# 09sata.net
KiCad netlist of a schematic drawn in Altium Designer
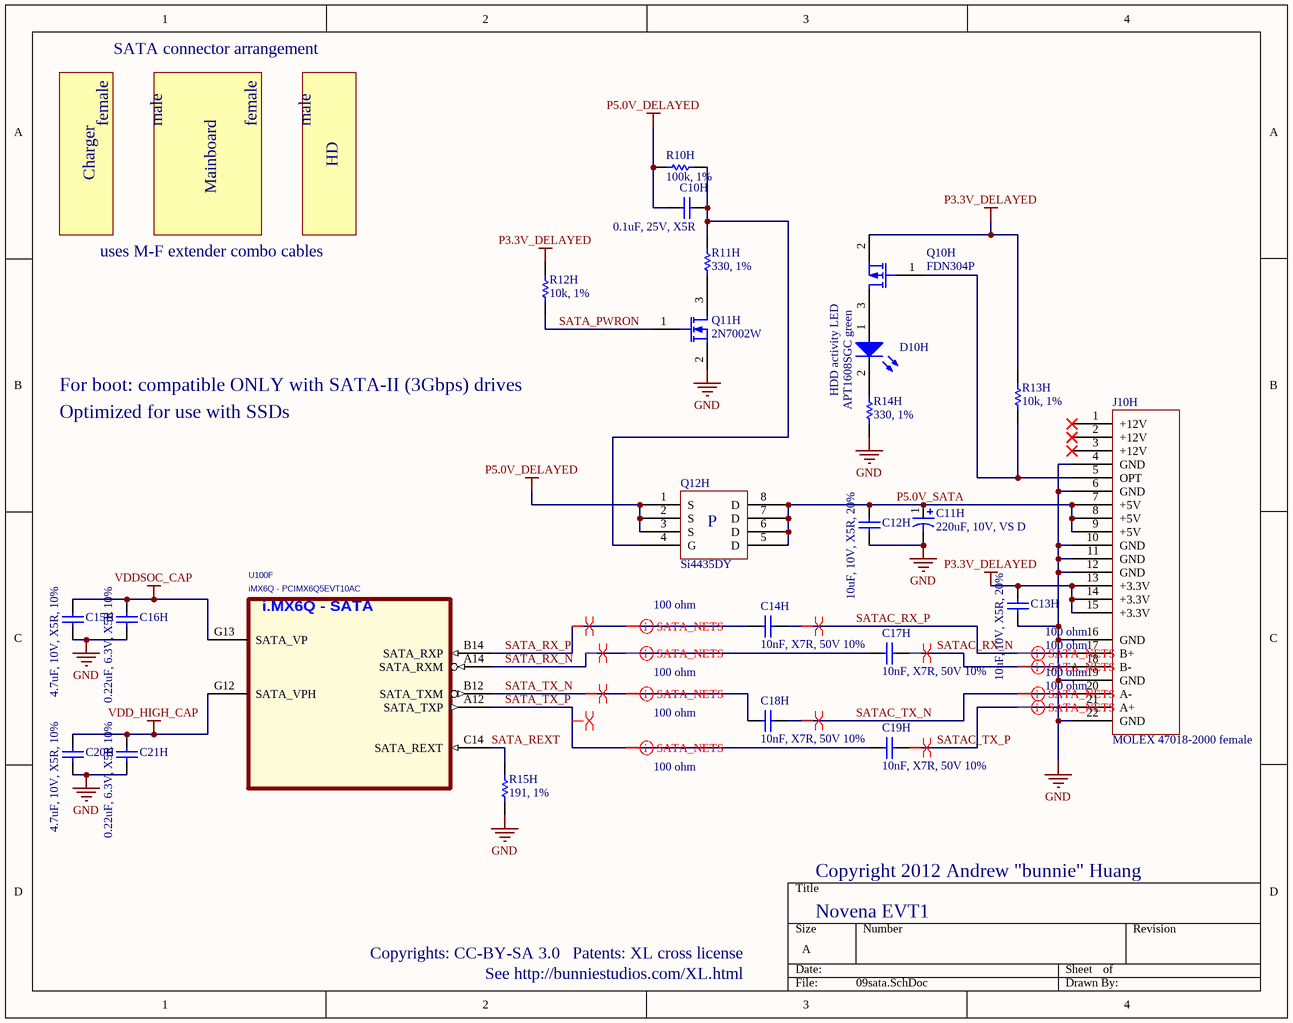
[diagram p0: 09sata.SchDoc]

(export (version "E")
  (design (tool "Eeschema 10.0.6"))
  (components
    (comp (ref "C10H")
      (value "0.1uF, 25V, X5R")
      (footprint "CAPC1005N")
      (description "Capacitor (Semiconductor SIM Model)")
      (fields (field (name "PUBLISHER") "Altium Limited"))
      (libsource (lib "Miscellaneous Devices") (part "Cap Semi"))
    )
    (comp (ref "C11H")
      (value "220uF, 10V, VS D")
      (footprint "6004pcb:ALCAP_D")
      (description "Polarized Capacitor (Surface Mount)")
      (fields (field (name "PUBLISHER") "Altium Limited"))
      (libsource (lib "Miscellaneous Devices") (part "Cap Pol3"))
    )
    (comp (ref "C12H")
      (value "10uF, 10V, X5R, 20%")
      (footprint "CAPC1608N")
      (description "Capacitor (Semiconductor SIM Model)")
      (fields (field (name "PUBLISHER") "Altium Limited"))
      (libsource (lib "Miscellaneous Devices") (part "Cap Semi"))
    )
    (comp (ref "C13H")
      (value "10uF, 10V, X5R, 20%")
      (footprint "CAPC1608N")
      (description "Capacitor (Semiconductor SIM Model)")
      (fields (field (name "PUBLISHER") "Altium Limited"))
      (libsource (lib "Miscellaneous Devices") (part "Cap Semi"))
    )
    (comp (ref "C14H")
      (value "10nF, X7R, 50V 10%")
      (footprint "CAPC1005N")
      (description "Capacitor (Semiconductor SIM Model)")
      (fields (field (name "PUBLISHER") "Altium Limited"))
      (libsource (lib "Miscellaneous Devices") (part "Cap Semi"))
    )
    (comp (ref "C15H")
      (value "4.7uF, 10V, X5R, 10%")
      (footprint "CAPC1608N_HD")
      (description "Capacitor (Semiconductor SIM Model)")
      (fields (field (name "PUBLISHER") "Altium Limited"))
      (libsource (lib "Miscellaneous Devices") (part "Cap Semi"))
    )
    (comp (ref "C16H")
      (value "0.22uF, 6.3V, X5R 10%")
      (footprint "CAPC0603N_B")
      (description "CAP CER 0.22UF 6.3V 20% X5R 0201")
      (fields (field (name "PUBLISHER") "Altium Limited"))
      (libsource (lib "Miscellaneous Devices") (part "Cap Semi"))
    )
    (comp (ref "C17H")
      (value "10nF, X7R, 50V 10%")
      (footprint "CAPC1005N")
      (description "Capacitor (Semiconductor SIM Model)")
      (fields (field (name "PUBLISHER") "Altium Limited"))
      (libsource (lib "Miscellaneous Devices") (part "Cap Semi"))
    )
    (comp (ref "C18H")
      (value "10nF, X7R, 50V 10%")
      (footprint "CAPC1005N")
      (description "Capacitor (Semiconductor SIM Model)")
      (fields (field (name "PUBLISHER") "Altium Limited"))
      (libsource (lib "Miscellaneous Devices") (part "Cap Semi"))
    )
    (comp (ref "C19H")
      (value "10nF, X7R, 50V 10%")
      (footprint "CAPC1005N")
      (description "Capacitor (Semiconductor SIM Model)")
      (fields (field (name "PUBLISHER") "Altium Limited"))
      (libsource (lib "Miscellaneous Devices") (part "Cap Semi"))
    )
    (comp (ref "C20H")
      (value "4.7uF, 10V, X5R, 10%")
      (footprint "CAPC1608N_HD")
      (description "Capacitor (Semiconductor SIM Model)")
      (fields (field (name "PUBLISHER") "Altium Limited"))
      (libsource (lib "Miscellaneous Devices") (part "Cap Semi"))
    )
    (comp (ref "C21H")
      (value "0.22uF, 6.3V, X5R 10%")
      (footprint "CAPC0603N_B")
      (description "CAP CER 0.22UF 6.3V 20% X5R 0201")
      (fields (field (name "PUBLISHER") "Altium Limited"))
      (libsource (lib "Miscellaneous Devices") (part "Cap Semi"))
    )
    (comp (ref "D10H")
      (value "APT1608SGC green")
      (footprint "CD1608-0603")
      (description "Typical RED, GREEN, YELLOW, AMBER GaAs LED")
      (fields (field (name "PUBLISHER") "Altium Limited"))
      (libsource (lib "Miscellaneous Devices") (part "LED2"))
    )
    (comp (ref "J10H")
      (value "MOLEX 47018-2000 female")
      (footprint "SATA_MOLEX_47018_2000")
      (description "SATA+Power connector")
      (libsource (lib "commonsch") (part "SATA_22P_HEADER"))
    )
    (comp (ref "Q10H")
      (value "FDN304P")
      (footprint "SOT23-3N")
      (description "P-Channel MOSFET")
      (fields (field (name "PUBLISHER") "Altium Limited"))
      (libsource (lib "Miscellaneous Devices") (part "MOSFET-P"))
    )
    (comp (ref "Q11H")
      (value "2N7002W")
      (footprint "SOT323-3AN")
      (description "N-Channel MOSFET")
      (fields (field (name "PUBLISHER") "Altium Limited"))
      (libsource (lib "Miscellaneous Devices") (part "MOSFET-N"))
    )
    (comp (ref "Q12H")
      (value "Si4435DY")
      (footprint "SOIC127P600-8AN")
      (description "Singre P-channel FET, 8A, 30V")
      (libsource (lib "commonsch") (part "Si4435DY"))
    )
    (comp (ref "R10H")
      (value "100k, 1%")
      (footprint "RESC1005N")
      (description "Resistor")
      (fields (field (name "PUBLISHER") "Altium Limited"))
      (libsource (lib "Miscellaneous Devices") (part "Res1"))
    )
    (comp (ref "R11H")
      (value "330, 1%")
      (footprint "RESC1005N")
      (description "Resistor")
      (fields (field (name "PUBLISHER") "Altium Limited"))
      (libsource (lib "Miscellaneous Devices") (part "Res1"))
    )
    (comp (ref "R12H")
      (value "10k, 1%")
      (footprint "RESC1005N")
      (description "Resistor")
      (fields (field (name "PUBLISHER") "Altium Limited"))
      (libsource (lib "Miscellaneous Devices") (part "Res1"))
    )
    (comp (ref "R13H")
      (value "10k, 1%")
      (footprint "RESC1005N")
      (description "Resistor")
      (fields (field (name "PUBLISHER") "Altium Limited"))
      (libsource (lib "Miscellaneous Devices") (part "Res1"))
    )
    (comp (ref "R14H")
      (value "330, 1%")
      (footprint "RESC1005N")
      (description "Resistor")
      (fields (field (name "PUBLISHER") "Altium Limited"))
      (libsource (lib "Miscellaneous Devices") (part "Res1"))
    )
    (comp (ref "R15H")
      (value "191, 1%")
      (footprint "RESC1005N")
      (description "Resistor")
      (fields (field (name "PUBLISHER") "Altium Limited"))
      (libsource (lib "Miscellaneous Devices") (part "Res1"))
    )
    (comp (ref "U100")
      (value "iMX6Q - PCIMX6Q5EVT10AC")
      (description "PLACEHOLDER FOR FREESCALE PART NUMBER PMCIMX6Q6VV1A.")
      (libsource (lib "*") (part "PCIMX6Q6VV1A"))
    )
  )
  (nets
    (net (code "1") (name "/P5.0V_SATA") (class "Default")
      (node (ref "C11H") (pin "1") (pinfunction "1_1") (pintype "passive"))
      (node (ref "C12H") (pin "1") (pinfunction "1_1") (pintype "passive"))
      (node (ref "J10H") (pin "7") (pinfunction "+5V_7") (pintype "power_in"))
      (node (ref "J10H") (pin "8") (pinfunction "+5V_8") (pintype "power_in"))
      (node (ref "J10H") (pin "9") (pinfunction "+5V_9") (pintype "power_in"))
      (node (ref "Q12H") (pin "5") (pinfunction "D_5") (pintype "passive"))
      (node (ref "Q12H") (pin "6") (pinfunction "D_6") (pintype "passive"))
      (node (ref "Q12H") (pin "7") (pinfunction "D_7") (pintype "passive"))
      (node (ref "Q12H") (pin "8") (pinfunction "D_8") (pintype "passive"))
    )
    (net (code "2") (name "/SATAC_RX_N") (class "Default")
      (node (ref "C17H") (pin "2") (pinfunction "2_2") (pintype "passive"))
      (node (ref "J10H") (pin "18") (pinfunction "B-_18") (pintype "passive"))
    )
    (net (code "3") (name "/SATAC_RX_P") (class "Default")
      (node (ref "C14H") (pin "2") (pinfunction "2_2") (pintype "passive"))
      (node (ref "J10H") (pin "17") (pinfunction "B+_17") (pintype "passive"))
    )
    (net (code "4") (name "/SATAC_TX_N") (class "Default")
      (node (ref "C18H") (pin "2") (pinfunction "2_2") (pintype "passive"))
      (node (ref "J10H") (pin "20") (pinfunction "A-_20") (pintype "passive"))
    )
    (net (code "5") (name "/SATAC_TX_P") (class "Default")
      (node (ref "C19H") (pin "2") (pinfunction "2_2") (pintype "passive"))
      (node (ref "J10H") (pin "21") (pinfunction "A+_21") (pintype "passive"))
    )
    (net (code "6") (name "/SATA_PWRON") (class "Default")
      (node (ref "Q11H") (pin "1") (pinfunction "G_1") (pintype "passive"))
      (node (ref "R12H") (pin "2") (pinfunction "2_2") (pintype "passive"))
    )
    (net (code "7") (name "/SATA_REXT") (class "Default")
      (node (ref "R15H") (pin "1") (pinfunction "1_1") (pintype "passive"))
      (node (ref "U100") (pin "C14") (pinfunction "SATA_REXT_C14") (pintype "input"))
    )
    (net (code "8") (name "/SATA_RX_N") (class "Default")
      (node (ref "C17H") (pin "1") (pinfunction "1_1") (pintype "passive"))
      (node (ref "U100") (pin "A14") (pinfunction "SATA_RXM_A14") (pintype "input"))
    )
    (net (code "9") (name "/SATA_RX_P") (class "Default")
      (node (ref "C14H") (pin "1") (pinfunction "1_1") (pintype "passive"))
      (node (ref "U100") (pin "B14") (pinfunction "SATA_RXP_B14") (pintype "input"))
    )
    (net (code "10") (name "/SATA_TX_N") (class "Default")
      (node (ref "C18H") (pin "1") (pinfunction "1_1") (pintype "passive"))
      (node (ref "U100") (pin "B12") (pinfunction "SATA_TXM_B12") (pintype "output"))
    )
    (net (code "11") (name "/SATA_TX_P") (class "Default")
      (node (ref "C19H") (pin "1") (pinfunction "1_1") (pintype "passive"))
      (node (ref "U100") (pin "A12") (pinfunction "SATA_TXP_A12") (pintype "output"))
    )
    (net (code "12") (name "GND") (class "Default")
      (node (ref "C11H") (pin "2") (pinfunction "2_2") (pintype "passive"))
      (node (ref "C12H") (pin "2") (pinfunction "2_2") (pintype "passive"))
      (node (ref "C13H") (pin "2") (pinfunction "2_2") (pintype "passive"))
      (node (ref "C15H") (pin "2") (pinfunction "2_2") (pintype "passive"))
      (node (ref "C16H") (pin "2") (pinfunction "2_2") (pintype "passive"))
      (node (ref "C20H") (pin "2") (pinfunction "2_2") (pintype "passive"))
      (node (ref "C21H") (pin "2") (pinfunction "2_2") (pintype "passive"))
      (node (ref "J10H") (pin "10") (pinfunction "GND_10") (pintype "power_in"))
      (node (ref "J10H") (pin "11") (pinfunction "GND_11") (pintype "power_in"))
      (node (ref "J10H") (pin "12") (pinfunction "GND_12") (pintype "power_in"))
      (node (ref "J10H") (pin "16") (pinfunction "GND_16") (pintype "power_in"))
      (node (ref "J10H") (pin "19") (pinfunction "GND_19") (pintype "power_in"))
      (node (ref "J10H") (pin "22") (pinfunction "GND_22") (pintype "power_in"))
      (node (ref "J10H") (pin "4") (pinfunction "GND_4") (pintype "power_in"))
      (node (ref "J10H") (pin "6") (pinfunction "GND_6") (pintype "power_in"))
      (node (ref "Q11H") (pin "2") (pinfunction "S_2") (pintype "passive"))
      (node (ref "R14H") (pin "1") (pinfunction "1_1") (pintype "passive"))
      (node (ref "R15H") (pin "2") (pinfunction "2_2") (pintype "passive"))
    )
    (net (code "13") (name "Net-(D10H-A)") (class "Default")
      (node (ref "D10H") (pin "1") (pinfunction "A_1") (pintype "passive"))
      (node (ref "Q10H") (pin "3") (pinfunction "D_3") (pintype "passive"))
    )
    (net (code "14") (name "Net-(D10H-K)") (class "Default")
      (node (ref "D10H") (pin "2") (pinfunction "K_2") (pintype "passive"))
      (node (ref "R14H") (pin "2") (pinfunction "2_2") (pintype "passive"))
    )
    (net (code "15") (name "Net-(J10H-OPT)") (class "Default")
      (node (ref "J10H") (pin "5") (pinfunction "OPT_5") (pintype "passive"))
      (node (ref "Q10H") (pin "1") (pinfunction "G_1") (pintype "passive"))
      (node (ref "R13H") (pin "2") (pinfunction "2_2") (pintype "passive"))
    )
    (net (code "16") (name "Net-(Q11H-D)") (class "Default")
      (node (ref "Q11H") (pin "3") (pinfunction "D_3") (pintype "passive"))
      (node (ref "R11H") (pin "2") (pinfunction "2_2") (pintype "passive"))
    )
    (net (code "17") (name "Net-(Q12H-G)") (class "Default")
      (node (ref "C10H") (pin "2") (pinfunction "2_2") (pintype "passive"))
      (node (ref "Q12H") (pin "4") (pinfunction "G_4") (pintype "passive"))
      (node (ref "R10H") (pin "1") (pinfunction "1_1") (pintype "passive"))
      (node (ref "R11H") (pin "1") (pinfunction "1_1") (pintype "passive"))
    )
    (net (code "18") (name "P3.3V_DELAYED") (class "Default")
      (node (ref "C13H") (pin "1") (pinfunction "1_1") (pintype "passive"))
      (node (ref "J10H") (pin "13") (pinfunction "+3.3V_13") (pintype "power_in"))
      (node (ref "J10H") (pin "14") (pinfunction "+3.3V_14") (pintype "power_in"))
      (node (ref "J10H") (pin "15") (pinfunction "+3.3V_15") (pintype "power_in"))
      (node (ref "Q10H") (pin "2") (pinfunction "S_2") (pintype "passive"))
      (node (ref "R12H") (pin "1") (pinfunction "1_1") (pintype "passive"))
      (node (ref "R13H") (pin "1") (pinfunction "1_1") (pintype "passive"))
    )
    (net (code "19") (name "P5.0V_DELAYED") (class "Default")
      (node (ref "C10H") (pin "1") (pinfunction "1_1") (pintype "passive"))
      (node (ref "Q12H") (pin "1") (pinfunction "S_1") (pintype "passive"))
      (node (ref "Q12H") (pin "2") (pinfunction "S_2") (pintype "passive"))
      (node (ref "Q12H") (pin "3") (pinfunction "S_3") (pintype "passive"))
      (node (ref "R10H") (pin "2") (pinfunction "2_2") (pintype "passive"))
    )
    (net (code "20") (name "VDDSOC_CAP") (class "Default")
      (node (ref "C15H") (pin "1") (pinfunction "1_1") (pintype "passive"))
      (node (ref "C16H") (pin "1") (pinfunction "1_1") (pintype "passive"))
      (node (ref "U100") (pin "G13") (pinfunction "SATA_VP_G13") (pintype "power_in"))
    )
    (net (code "21") (name "VDD_HIGH_CAP") (class "Default")
      (node (ref "C20H") (pin "1") (pinfunction "1_1") (pintype "passive"))
      (node (ref "C21H") (pin "1") (pinfunction "1_1") (pintype "passive"))
      (node (ref "U100") (pin "G12") (pinfunction "SATA_VPH_G12") (pintype "power_in"))
    )
    (net (code "22") (name "unconnected-(J10H-+12V-Pad1)") (class "Default")
      (node (ref "J10H") (pin "1") (pinfunction "+12V_1") (pintype "power_in+no_connect"))
    )
    (net (code "23") (name "unconnected-(J10H-+12V-Pad2)") (class "Default")
      (node (ref "J10H") (pin "2") (pinfunction "+12V_2") (pintype "power_in+no_connect"))
    )
    (net (code "24") (name "unconnected-(J10H-+12V-Pad3)") (class "Default")
      (node (ref "J10H") (pin "3") (pinfunction "+12V_3") (pintype "power_in+no_connect"))
    )
  )
)
